# MainBoard.net
KiCad netlist of a schematic drawn in EAGLE
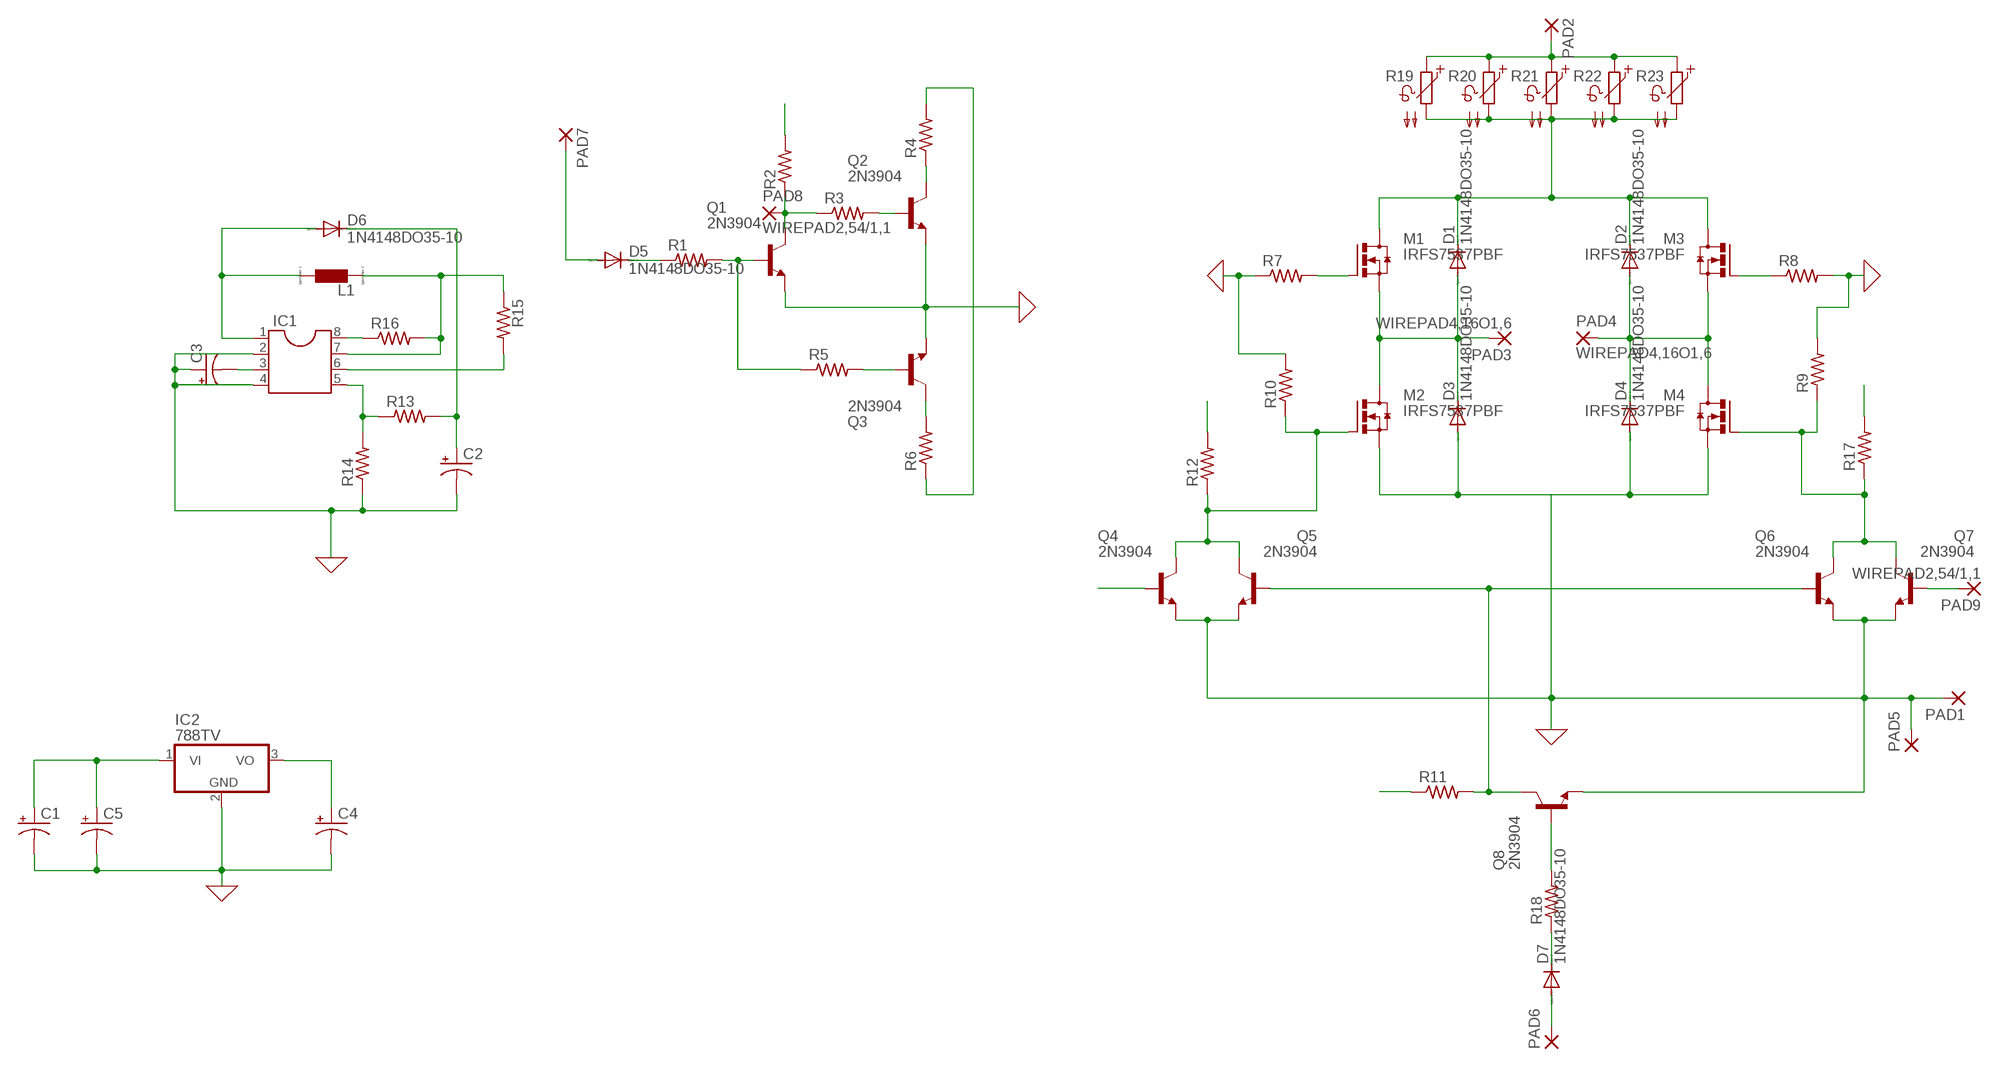
[diagram p0: schematic, sheet 1]

(export (version "E")
  (design (tool "Eeschema 10.0.6"))
  (components
    (comp (ref "C1")
      (value "CPOL-USE2.5-7")
      (footprint "eagle-import:E2,5-7")
      (libsource (lib "eagle-import") (part "CPOL-USE2.5-7"))
    )
    (comp (ref "C2")
      (value "CPOL-USE2.5-7")
      (footprint "eagle-import:E2,5-7")
      (libsource (lib "eagle-import") (part "CPOL-USE2.5-7"))
    )
    (comp (ref "C3")
      (value "CPOL-USE2.5-7")
      (footprint "eagle-import:E2,5-7")
      (libsource (lib "eagle-import") (part "CPOL-USE2.5-7"))
    )
    (comp (ref "C4")
      (value "CPOL-USE2.5-7")
      (footprint "eagle-import:E2,5-7")
      (libsource (lib "eagle-import") (part "CPOL-USE2.5-7"))
    )
    (comp (ref "C5")
      (value "CPOL-USE2.5-7")
      (footprint "eagle-import:E2,5-7")
      (libsource (lib "eagle-import") (part "CPOL-USE2.5-7"))
    )
    (comp (ref "D1")
      (value "1N4148DO35-10")
      (footprint "eagle-import:DO35-10")
      (libsource (lib "eagle-import") (part "1N4148DO35-10"))
    )
    (comp (ref "D2")
      (value "1N4148DO35-10")
      (footprint "eagle-import:DO35-10")
      (libsource (lib "eagle-import") (part "1N4148DO35-10"))
    )
    (comp (ref "D3")
      (value "1N4148DO35-10")
      (footprint "eagle-import:DO35-10")
      (libsource (lib "eagle-import") (part "1N4148DO35-10"))
    )
    (comp (ref "D4")
      (value "1N4148DO35-10")
      (footprint "eagle-import:DO35-10")
      (libsource (lib "eagle-import") (part "1N4148DO35-10"))
    )
    (comp (ref "D5")
      (value "1N4148DO35-10")
      (footprint "eagle-import:DO35-10")
      (libsource (lib "eagle-import") (part "1N4148DO35-10"))
    )
    (comp (ref "D6")
      (value "1N4148DO35-10")
      (footprint "eagle-import:DO35-10")
      (libsource (lib "eagle-import") (part "1N4148DO35-10"))
    )
    (comp (ref "D7")
      (value "1N4148DO35-10")
      (footprint "eagle-import:DO35-10")
      (libsource (lib "eagle-import") (part "1N4148DO35-10"))
    )
    (comp (ref "IC1")
      (value "DIL8")
      (footprint "eagle-import:DIL08")
      (libsource (lib "eagle-import") (part "DIL8"))
    )
    (comp (ref "IC2")
      (value "788TV")
      (footprint "eagle-import:TO220V")
      (libsource (lib "eagle-import") (part "78TV8"))
    )
    (comp (ref "L1")
      (value "L0207/10")
      (footprint "eagle-import:0207_10")
      (libsource (lib "eagle-import") (part "L0207/10"))
    )
    (comp (ref "M1")
      (value "IRFS7537PBF")
      (footprint "eagle-import:D2PACK")
      (libsource (lib "eagle-import") (part "IRFS7537PBF"))
    )
    (comp (ref "M2")
      (value "IRFS7537PBF")
      (footprint "eagle-import:D2PACK")
      (libsource (lib "eagle-import") (part "IRFS7537PBF"))
    )
    (comp (ref "M3")
      (value "IRFS7537PBF")
      (footprint "eagle-import:D2PACK")
      (libsource (lib "eagle-import") (part "IRFS7537PBF"))
    )
    (comp (ref "M4")
      (value "IRFS7537PBF")
      (footprint "eagle-import:D2PACK")
      (libsource (lib "eagle-import") (part "IRFS7537PBF"))
    )
    (comp (ref "PAD1")
      (value "3,81/1,4")
      (footprint "eagle-import:3,81_1,4")
      (libsource (lib "eagle-import") (part "3,81/1,4"))
    )
    (comp (ref "PAD2")
      (value "3,81/1,4")
      (footprint "eagle-import:3,81_1,4")
      (libsource (lib "eagle-import") (part "3,81/1,4"))
    )
    (comp (ref "PAD3")
      (value "WIREPAD4,16O1,6")
      (footprint "eagle-import:4,16O1,6")
      (libsource (lib "eagle-import") (part "WIREPAD4,16O1,6"))
    )
    (comp (ref "PAD4")
      (value "WIREPAD4,16O1,6")
      (footprint "eagle-import:4,16O1,6")
      (libsource (lib "eagle-import") (part "WIREPAD4,16O1,6"))
    )
    (comp (ref "PAD5")
      (value "3,81/1,4")
      (footprint "eagle-import:3,81_1,4")
      (libsource (lib "eagle-import") (part "3,81/1,4"))
    )
    (comp (ref "PAD6")
      (value "2,54/1,0")
      (footprint "eagle-import:2,54_1,0")
      (libsource (lib "eagle-import") (part "2,54/1,0"))
    )
    (comp (ref "PAD7")
      (value "2,54/1,0")
      (footprint "eagle-import:2,54_1,0")
      (libsource (lib "eagle-import") (part "2,54/1,0"))
    )
    (comp (ref "PAD8")
      (value "WIREPAD2,54/1,1")
      (footprint "eagle-import:2,54_1,1")
      (libsource (lib "eagle-import") (part "WIREPAD2,54/1,1"))
    )
    (comp (ref "PAD9")
      (value "WIREPAD2,54/1,1")
      (footprint "eagle-import:2,54_1,1")
      (libsource (lib "eagle-import") (part "WIREPAD2,54/1,1"))
    )
    (comp (ref "Q1")
      (value "2N3904")
      (footprint "eagle-import:TO92")
      (libsource (lib "eagle-import") (part "2N3904"))
    )
    (comp (ref "Q2")
      (value "2N3904")
      (footprint "eagle-import:TO92")
      (libsource (lib "eagle-import") (part "2N3904"))
    )
    (comp (ref "Q3")
      (value "2N3904")
      (footprint "eagle-import:TO92")
      (libsource (lib "eagle-import") (part "2N3904"))
    )
    (comp (ref "Q4")
      (value "2N3904")
      (footprint "eagle-import:TO92")
      (libsource (lib "eagle-import") (part "2N3904"))
    )
    (comp (ref "Q5")
      (value "2N3904")
      (footprint "eagle-import:TO92")
      (libsource (lib "eagle-import") (part "2N3904"))
    )
    (comp (ref "Q6")
      (value "2N3904")
      (footprint "eagle-import:TO92")
      (libsource (lib "eagle-import") (part "2N3904"))
    )
    (comp (ref "Q7")
      (value "2N3904")
      (footprint "eagle-import:TO92")
      (libsource (lib "eagle-import") (part "2N3904"))
    )
    (comp (ref "Q8")
      (value "2N3904")
      (footprint "eagle-import:TO92")
      (libsource (lib "eagle-import") (part "2N3904"))
    )
    (comp (ref "R1")
      (value "R-US_0207/7")
      (footprint "eagle-import:0207_7")
      (libsource (lib "eagle-import") (part "R-US_0207/7"))
    )
    (comp (ref "R2")
      (value "R-US_0207/7")
      (footprint "eagle-import:0207_7")
      (libsource (lib "eagle-import") (part "R-US_0207/7"))
    )
    (comp (ref "R3")
      (value "R-US_0207/7")
      (footprint "eagle-import:0207_7")
      (libsource (lib "eagle-import") (part "R-US_0207/7"))
    )
    (comp (ref "R4")
      (value "R-US_0207/7")
      (footprint "eagle-import:0207_7")
      (libsource (lib "eagle-import") (part "R-US_0207/7"))
    )
    (comp (ref "R5")
      (value "R-US_0207/7")
      (footprint "eagle-import:0207_7")
      (libsource (lib "eagle-import") (part "R-US_0207/7"))
    )
    (comp (ref "R6")
      (value "R-US_0207/7")
      (footprint "eagle-import:0207_7")
      (libsource (lib "eagle-import") (part "R-US_0207/7"))
    )
    (comp (ref "R7")
      (value "R-US_0207/7")
      (footprint "eagle-import:0207_7")
      (libsource (lib "eagle-import") (part "R-US_0207/7"))
    )
    (comp (ref "R8")
      (value "R-US_0207/7")
      (footprint "eagle-import:0207_7")
      (libsource (lib "eagle-import") (part "R-US_0207/7"))
    )
    (comp (ref "R9")
      (value "R-US_0207/7")
      (footprint "eagle-import:0207_7")
      (libsource (lib "eagle-import") (part "R-US_0207/7"))
    )
    (comp (ref "R10")
      (value "R-US_0207/7")
      (footprint "eagle-import:0207_7")
      (libsource (lib "eagle-import") (part "R-US_0207/7"))
    )
    (comp (ref "R11")
      (value "R-US_0207/7")
      (footprint "eagle-import:0207_7")
      (libsource (lib "eagle-import") (part "R-US_0207/7"))
    )
    (comp (ref "R12")
      (value "R-US_0207/7")
      (footprint "eagle-import:0207_7")
      (libsource (lib "eagle-import") (part "R-US_0207/7"))
    )
    (comp (ref "R13")
      (value "R-US_0207/7")
      (footprint "eagle-import:0207_7")
      (libsource (lib "eagle-import") (part "R-US_0207/7"))
    )
    (comp (ref "R14")
      (value "R-US_0207/7")
      (footprint "eagle-import:0207_7")
      (libsource (lib "eagle-import") (part "R-US_0207/7"))
    )
    (comp (ref "R15")
      (value "R-US_0207/7")
      (footprint "eagle-import:0207_7")
      (libsource (lib "eagle-import") (part "R-US_0207/7"))
    )
    (comp (ref "R16")
      (value "R-US_0207/7")
      (footprint "eagle-import:0207_7")
      (libsource (lib "eagle-import") (part "R-US_0207/7"))
    )
    (comp (ref "R17")
      (value "R-US_0309/12")
      (footprint "eagle-import:0309_12")
      (libsource (lib "eagle-import") (part "resistor_348_R-US_0309/12"))
    )
    (comp (ref "R18")
      (value "R-US_0207/7")
      (footprint "eagle-import:0207_7")
      (libsource (lib "eagle-import") (part "R-US_0207/7"))
    )
    (comp (ref "R19")
      (value "PTC660A")
      (footprint "eagle-import:P660A")
      (libsource (lib "eagle-import") (part "PTC660A"))
    )
    (comp (ref "R20")
      (value "PTC660A")
      (footprint "eagle-import:P660A")
      (libsource (lib "eagle-import") (part "PTC660A"))
    )
    (comp (ref "R21")
      (value "PTC660A")
      (footprint "eagle-import:P660A")
      (libsource (lib "eagle-import") (part "PTC660A"))
    )
    (comp (ref "R22")
      (value "PTC660A")
      (footprint "eagle-import:P660A")
      (libsource (lib "eagle-import") (part "PTC660A"))
    )
    (comp (ref "R23")
      (value "PTC660A")
      (footprint "eagle-import:P660A")
      (libsource (lib "eagle-import") (part "PTC660A"))
    )
  )
  (nets
    (net (code "1") (name "/BB") (class "Default")
      (node (ref "Q1") (pin "2") (pinfunction "B_2") (pintype "passive"))
      (node (ref "Q4") (pin "2") (pinfunction "B_2") (pintype "passive"))
      (node (ref "R1") (pin "2") (pinfunction "2_2") (pintype "passive"))
      (node (ref "R5") (pin "1") (pinfunction "1_1") (pintype "passive"))
    )
    (net (code "2") (name "/BF") (class "Default")
      (node (ref "M3") (pin "1") (pinfunction "G_1") (pintype "passive"))
      (node (ref "Q3") (pin "1") (pinfunction "C_1") (pintype "passive"))
      (node (ref "R6") (pin "2") (pinfunction "2_2") (pintype "passive"))
      (node (ref "R8") (pin "1") (pinfunction "1_1") (pintype "passive"))
    )
    (net (code "3") (name "/FF") (class "Default")
      (node (ref "M1") (pin "1") (pinfunction "G_1") (pintype "passive"))
      (node (ref "Q2") (pin "1") (pinfunction "C_1") (pintype "passive"))
      (node (ref "R4") (pin "1") (pinfunction "1_1") (pintype "passive"))
      (node (ref "R7") (pin "2") (pinfunction "2_2") (pintype "passive"))
    )
    (net (code "4") (name "/VDD") (class "Default")
      (node (ref "C1") (pin "+") (pinfunction "+_+") (pintype "passive"))
      (node (ref "C5") (pin "+") (pinfunction "+_+") (pintype "passive"))
      (node (ref "D1") (pin "C") (pinfunction "C_C") (pintype "passive"))
      (node (ref "D2") (pin "C") (pinfunction "C_C") (pintype "passive"))
      (node (ref "IC1") (pin "6") (pinfunction "6_6") (pintype "passive"))
      (node (ref "IC2") (pin "1") (pinfunction "VI_1") (pintype "input"))
      (node (ref "M1") (pin "2") (pinfunction "D_2") (pintype "passive"))
      (node (ref "M3") (pin "2") (pinfunction "D_2") (pintype "passive"))
      (node (ref "R12") (pin "2") (pinfunction "2_2") (pintype "passive"))
      (node (ref "R15") (pin "2") (pinfunction "2_2") (pintype "passive"))
      (node (ref "R17") (pin "2") (pinfunction "2_2") (pintype "passive"))
      (node (ref "R19") (pin "2") (pinfunction "2_2") (pintype "passive"))
      (node (ref "R20") (pin "2") (pinfunction "2_2") (pintype "passive"))
      (node (ref "R21") (pin "2") (pinfunction "2_2") (pintype "passive"))
      (node (ref "R22") (pin "2") (pinfunction "2_2") (pintype "passive"))
      (node (ref "R23") (pin "2") (pinfunction "2_2") (pintype "passive"))
    )
    (net (code "5") (name "/VSW") (class "Default")
      (node (ref "C4") (pin "+") (pinfunction "+_+") (pintype "passive"))
      (node (ref "IC2") (pin "3") (pinfunction "VO_3") (pintype "passive"))
      (node (ref "R11") (pin "1") (pinfunction "1_1") (pintype "passive"))
      (node (ref "R2") (pin "2") (pinfunction "2_2") (pintype "passive"))
    )
    (net (code "6") (name "GND") (class "Default")
      (node (ref "C1") (pin "-") (pinfunction "-_-") (pintype "passive"))
      (node (ref "C2") (pin "-") (pinfunction "-_-") (pintype "passive"))
      (node (ref "C3") (pin "+") (pinfunction "+_+") (pintype "passive"))
      (node (ref "C4") (pin "-") (pinfunction "-_-") (pintype "passive"))
      (node (ref "C5") (pin "-") (pinfunction "-_-") (pintype "passive"))
      (node (ref "D3") (pin "A") (pinfunction "A_A") (pintype "passive"))
      (node (ref "D4") (pin "A") (pinfunction "A_A") (pintype "passive"))
      (node (ref "IC1") (pin "2") (pinfunction "2_2") (pintype "passive"))
      (node (ref "IC1") (pin "4") (pinfunction "4_4") (pintype "passive"))
      (node (ref "IC2") (pin "2") (pinfunction "GND_2") (pintype "passive"))
      (node (ref "M2") (pin "3") (pinfunction "S_3") (pintype "passive"))
      (node (ref "M4") (pin "3") (pinfunction "S_3") (pintype "passive"))
      (node (ref "PAD1") (pin "1") (pinfunction "P_1") (pintype "passive"))
      (node (ref "PAD5") (pin "1") (pinfunction "P_1") (pintype "passive"))
      (node (ref "Q1") (pin "3") (pinfunction "E_3") (pintype "passive"))
      (node (ref "Q2") (pin "3") (pinfunction "E_3") (pintype "passive"))
      (node (ref "Q3") (pin "3") (pinfunction "E_3") (pintype "passive"))
      (node (ref "Q4") (pin "3") (pinfunction "E_3") (pintype "passive"))
      (node (ref "Q5") (pin "3") (pinfunction "E_3") (pintype "passive"))
      (node (ref "Q6") (pin "3") (pinfunction "E_3") (pintype "passive"))
      (node (ref "Q7") (pin "3") (pinfunction "E_3") (pintype "passive"))
      (node (ref "Q8") (pin "3") (pinfunction "E_3") (pintype "passive"))
      (node (ref "R10") (pin "2") (pinfunction "2_2") (pintype "passive"))
      (node (ref "R14") (pin "1") (pinfunction "1_1") (pintype "passive"))
      (node (ref "R7") (pin "1") (pinfunction "1_1") (pintype "passive"))
      (node (ref "R8") (pin "2") (pinfunction "2_2") (pintype "passive"))
      (node (ref "R9") (pin "2") (pinfunction "2_2") (pintype "passive"))
    )
    (net (code "7") (name "Net-(C2-Pad+)") (class "Default")
      (node (ref "C2") (pin "+") (pinfunction "+_+") (pintype "passive"))
      (node (ref "D6") (pin "C") (pinfunction "C_C") (pintype "passive"))
      (node (ref "R13") (pin "2") (pinfunction "2_2") (pintype "passive"))
    )
    (net (code "8") (name "Net-(C3-Pad-)") (class "Default")
      (node (ref "C3") (pin "-") (pinfunction "-_-") (pintype "passive"))
      (node (ref "IC1") (pin "3") (pinfunction "3_3") (pintype "passive"))
    )
    (net (code "9") (name "Net-(D5-PadC)") (class "Default")
      (node (ref "D5") (pin "C") (pinfunction "C_C") (pintype "passive"))
      (node (ref "R1") (pin "1") (pinfunction "1_1") (pintype "passive"))
    )
    (net (code "10") (name "Net-(D6-PadA)") (class "Default")
      (node (ref "D6") (pin "A") (pinfunction "A_A") (pintype "passive"))
      (node (ref "IC1") (pin "1") (pinfunction "1_1") (pintype "passive"))
      (node (ref "L1") (pin "1") (pinfunction "1_1") (pintype "passive"))
    )
    (net (code "11") (name "Net-(D7-PadC)") (class "Default")
      (node (ref "D7") (pin "C") (pinfunction "C_C") (pintype "passive"))
      (node (ref "R18") (pin "1") (pinfunction "1_1") (pintype "passive"))
    )
    (net (code "12") (name "Net-(IC1-Pad5)") (class "Default")
      (node (ref "IC1") (pin "5") (pinfunction "5_5") (pintype "passive"))
      (node (ref "R13") (pin "1") (pinfunction "1_1") (pintype "passive"))
      (node (ref "R14") (pin "2") (pinfunction "2_2") (pintype "passive"))
    )
    (net (code "13") (name "Net-(IC1-Pad7)") (class "Default")
      (node (ref "IC1") (pin "7") (pinfunction "7_7") (pintype "passive"))
      (node (ref "L1") (pin "2") (pinfunction "2_2") (pintype "passive"))
      (node (ref "R15") (pin "1") (pinfunction "1_1") (pintype "passive"))
      (node (ref "R16") (pin "2") (pinfunction "2_2") (pintype "passive"))
    )
    (net (code "14") (name "Net-(IC1-Pad8)") (class "Default")
      (node (ref "IC1") (pin "8") (pinfunction "8_8") (pintype "passive"))
      (node (ref "R16") (pin "1") (pinfunction "1_1") (pintype "passive"))
    )
    (net (code "15") (name "Net-(M1-S)") (class "Default")
      (node (ref "D1") (pin "A") (pinfunction "A_A") (pintype "passive"))
      (node (ref "D3") (pin "C") (pinfunction "C_C") (pintype "passive"))
      (node (ref "M1") (pin "3") (pinfunction "S_3") (pintype "passive"))
      (node (ref "M2") (pin "2") (pinfunction "D_2") (pintype "passive"))
      (node (ref "PAD3") (pin "1") (pinfunction "P_1") (pintype "passive"))
    )
    (net (code "16") (name "Net-(M2-G)") (class "Default")
      (node (ref "M2") (pin "1") (pinfunction "G_1") (pintype "passive"))
      (node (ref "Q4") (pin "1") (pinfunction "C_1") (pintype "passive"))
      (node (ref "Q5") (pin "1") (pinfunction "C_1") (pintype "passive"))
      (node (ref "R10") (pin "1") (pinfunction "1_1") (pintype "passive"))
      (node (ref "R12") (pin "1") (pinfunction "1_1") (pintype "passive"))
    )
    (net (code "17") (name "Net-(M3-S)") (class "Default")
      (node (ref "D2") (pin "A") (pinfunction "A_A") (pintype "passive"))
      (node (ref "D4") (pin "C") (pinfunction "C_C") (pintype "passive"))
      (node (ref "M3") (pin "3") (pinfunction "S_3") (pintype "passive"))
      (node (ref "M4") (pin "2") (pinfunction "D_2") (pintype "passive"))
      (node (ref "PAD4") (pin "1") (pinfunction "P_1") (pintype "passive"))
    )
    (net (code "18") (name "Net-(M4-G)") (class "Default")
      (node (ref "M4") (pin "1") (pinfunction "G_1") (pintype "passive"))
      (node (ref "Q6") (pin "1") (pinfunction "C_1") (pintype "passive"))
      (node (ref "Q7") (pin "1") (pinfunction "C_1") (pintype "passive"))
      (node (ref "R17") (pin "1") (pinfunction "1_1") (pintype "passive"))
      (node (ref "R9") (pin "1") (pinfunction "1_1") (pintype "passive"))
    )
    (net (code "19") (name "Net-(PAD2-P)") (class "Default")
      (node (ref "PAD2") (pin "1") (pinfunction "P_1") (pintype "passive"))
      (node (ref "R19") (pin "1") (pinfunction "1_1") (pintype "passive"))
      (node (ref "R20") (pin "1") (pinfunction "1_1") (pintype "passive"))
      (node (ref "R21") (pin "1") (pinfunction "1_1") (pintype "passive"))
      (node (ref "R22") (pin "1") (pinfunction "1_1") (pintype "passive"))
      (node (ref "R23") (pin "1") (pinfunction "1_1") (pintype "passive"))
    )
    (net (code "20") (name "Net-(PAD6-P)") (class "Default")
      (node (ref "D7") (pin "A") (pinfunction "A_A") (pintype "passive"))
      (node (ref "PAD6") (pin "1") (pinfunction "P_1") (pintype "passive"))
    )
    (net (code "21") (name "Net-(PAD7-P)") (class "Default")
      (node (ref "D5") (pin "A") (pinfunction "A_A") (pintype "passive"))
      (node (ref "PAD7") (pin "1") (pinfunction "P_1") (pintype "passive"))
    )
    (net (code "22") (name "Net-(PAD8-P)") (class "Default")
      (node (ref "PAD8") (pin "1") (pinfunction "P_1") (pintype "passive"))
      (node (ref "Q1") (pin "1") (pinfunction "C_1") (pintype "passive"))
      (node (ref "R2") (pin "1") (pinfunction "1_1") (pintype "passive"))
      (node (ref "R3") (pin "1") (pinfunction "1_1") (pintype "passive"))
    )
    (net (code "23") (name "Net-(PAD9-P)") (class "Default")
      (node (ref "PAD9") (pin "1") (pinfunction "P_1") (pintype "passive"))
      (node (ref "Q7") (pin "2") (pinfunction "B_2") (pintype "passive"))
    )
    (net (code "24") (name "Net-(Q2-B)") (class "Default")
      (node (ref "Q2") (pin "2") (pinfunction "B_2") (pintype "passive"))
      (node (ref "R3") (pin "2") (pinfunction "2_2") (pintype "passive"))
    )
    (net (code "25") (name "Net-(Q3-B)") (class "Default")
      (node (ref "Q3") (pin "2") (pinfunction "B_2") (pintype "passive"))
      (node (ref "R5") (pin "2") (pinfunction "2_2") (pintype "passive"))
    )
    (net (code "26") (name "Net-(Q5-B)") (class "Default")
      (node (ref "Q5") (pin "2") (pinfunction "B_2") (pintype "passive"))
      (node (ref "Q6") (pin "2") (pinfunction "B_2") (pintype "passive"))
      (node (ref "Q8") (pin "1") (pinfunction "C_1") (pintype "passive"))
      (node (ref "R11") (pin "2") (pinfunction "2_2") (pintype "passive"))
    )
    (net (code "27") (name "Net-(Q8-B)") (class "Default")
      (node (ref "Q8") (pin "2") (pinfunction "B_2") (pintype "passive"))
      (node (ref "R18") (pin "2") (pinfunction "2_2") (pintype "passive"))
    )
    (net (code "28") (name "Net-(R4-Pad2)") (class "Default")
      (node (ref "R4") (pin "2") (pinfunction "2_2") (pintype "passive"))
      (node (ref "R6") (pin "1") (pinfunction "1_1") (pintype "passive"))
    )
  )
)
